# 5V_power_4A.net
KiCad netlist of a schematic drawn in Altium Designer
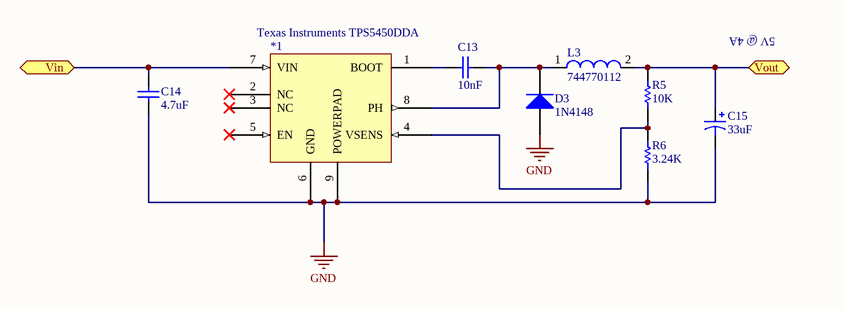
[diagram p0: 5V_power_4A.SchDoc]

(export (version "E")
  (design (tool "Eeschema 10.0.6"))
  (components
    (comp (ref "*1")
      (value "Texas Instruments TPS5450DDA")
      (footprint "PCB-i2ey7la0otg9s5bbbcx3-1")
      (description "Conv DC-DC 5.5V to 36V Step Down Single-Out 1.22V to 31V 5A 8-Pin HSOP EP Tube")
      (libsource (lib "Octopart library") (part "SYM-a3426a1a5de77c85-1"))
    )
    (comp (ref "C13")
      (value "10nF")
      (footprint "GRM21BR61H475KE51L")
      (description "CAP CER 4.7UF 50V X5R 0805")
      (libsource (lib "CommunityVault") (part "CMP-12577565-9"))
    )
    (comp (ref "C14")
      (value "4.7uF")
      (footprint "GRM21BR61H475KE51L")
      (description "CAP CER 4.7UF 50V X5R 0805")
      (libsource (lib "CommunityVault") (part "CMP-12577565-9"))
    )
    (comp (ref "C15")
      (value "33uF")
      (footprint "PCB-m8hbcurj3co3kv9xxxha-1")
      (description "Cap Alum 33UF 20% 35V Radial")
      (fields (field (name "MANUFACTURER PART NUMBER") "35MS533MEFC8X5"))
      (libsource (lib "FavoritesLibrary") (part "SYM-3dc2f5bba3b9e205-1"))
    )
    (comp (ref "D3")
      (value "1N4148")
      (footprint "PCB-1N4148W-7-F")
      (description "Fast Switching Diode, 100V, 400mW, Surface Mount, SOD-123")
      (fields (field (name "MANUFACTURER PART NUMBER") "1N4148W-7-F"))
      (libsource (lib "CommunityVault") (part "1N4148"))
    )
    (comp (ref "L3")
      (value "744770112")
      (footprint "WE-PD-XL")
      (description "SMD-Shielded Power Inductor WE-PD, L = 12.0 µH")
      (libsource (lib "Octopart library") (part "PAS-IND-INDUCTOR-2"))
    )
    (comp (ref "R5")
      (value "10K")
      (footprint "PCB-9ahxsq8gddjqcnfjmojj-1")
      (description "RMCF Series 0603 Case 10 kOhm ±1 % ±100 ppm/°C SMT Thick Film Chip Resistor")
      (fields (field (name "MANUFACTURER PART NUMBER") "RMCF0603FT10K0"))
      (libsource (lib "Octopart library") (part "SYM-02dfcaf00d3bdd18-1"))
    )
    (comp (ref "R6")
      (value "3.24K")
      (footprint "PCB-9ahxsq8gddjqcnfjmojj-1")
      (description "RMCF Series 0603 Case 10 kOhm ±1 % ±100 ppm/°C SMT Thick Film Chip Resistor")
      (fields (field (name "MANUFACTURER PART NUMBER") "RMCF0603FT10K0"))
      (libsource (lib "Octopart library") (part "SYM-02dfcaf00d3bdd18-1"))
    )
  )
  (nets
    (net (code "1") (name "/Vin") (class "Default")
      (node (ref "*1") (pin "7") (pinfunction "VIN_7") (pintype "input"))
      (node (ref "C14") (pin "2") (pinfunction "2_2") (pintype "passive"))
    )
    (net (code "2") (name "/Vout") (class "Default")
      (node (ref "C15") (pin "1") (pinfunction "1_1") (pintype "passive"))
      (node (ref "L3") (pin "2") (pinfunction "2_2") (pintype "passive"))
      (node (ref "R5") (pin "2") (pinfunction "2_2") (pintype "passive"))
    )
    (net (code "3") (name "GND") (class "Default")
      (node (ref "*1") (pin "6") (pinfunction "GND_6") (pintype "power_in"))
      (node (ref "*1") (pin "9") (pinfunction "POWERPAD_9") (pintype "power_in"))
      (node (ref "C14") (pin "1") (pinfunction "1_1") (pintype "passive"))
      (node (ref "C15") (pin "2") (pinfunction "2_2") (pintype "passive"))
      (node (ref "D3") (pin "1") (pinfunction "A_1") (pintype "passive"))
      (node (ref "R6") (pin "1") (pinfunction "1_1") (pintype "passive"))
    )
    (net (code "4") (name "Net-(*1-BOOT)") (class "Default")
      (node (ref "*1") (pin "1") (pinfunction "BOOT_1") (pintype "passive"))
      (node (ref "C13") (pin "2") (pinfunction "2_2") (pintype "passive"))
    )
    (net (code "5") (name "Net-(*1-PH)") (class "Default")
      (node (ref "*1") (pin "8") (pinfunction "PH_8") (pintype "output"))
      (node (ref "C13") (pin "1") (pinfunction "1_1") (pintype "passive"))
      (node (ref "D3") (pin "2") (pinfunction "K_2") (pintype "passive"))
      (node (ref "L3") (pin "1") (pinfunction "1_1") (pintype "passive"))
    )
    (net (code "6") (name "Net-(*1-VSENS)") (class "Default")
      (node (ref "*1") (pin "4") (pinfunction "VSENS_4") (pintype "input"))
      (node (ref "R5") (pin "1") (pinfunction "1_1") (pintype "passive"))
      (node (ref "R6") (pin "2") (pinfunction "2_2") (pintype "passive"))
    )
    (net (code "7") (name "unconnected-(*1-EN-Pad5)") (class "Default")
      (node (ref "*1") (pin "5") (pinfunction "EN_5") (pintype "input+no_connect"))
    )
    (net (code "8") (name "unconnected-(*1-NC-Pad2)") (class "Default")
      (node (ref "*1") (pin "2") (pinfunction "NC_2") (pintype "passive+no_connect"))
    )
    (net (code "9") (name "unconnected-(*1-NC-Pad3)") (class "Default")
      (node (ref "*1") (pin "3") (pinfunction "NC_3") (pintype "passive+no_connect"))
    )
  )
)
